# ArduinoUnoShield.net
KiCad netlist of a schematic drawn in Altium Designer
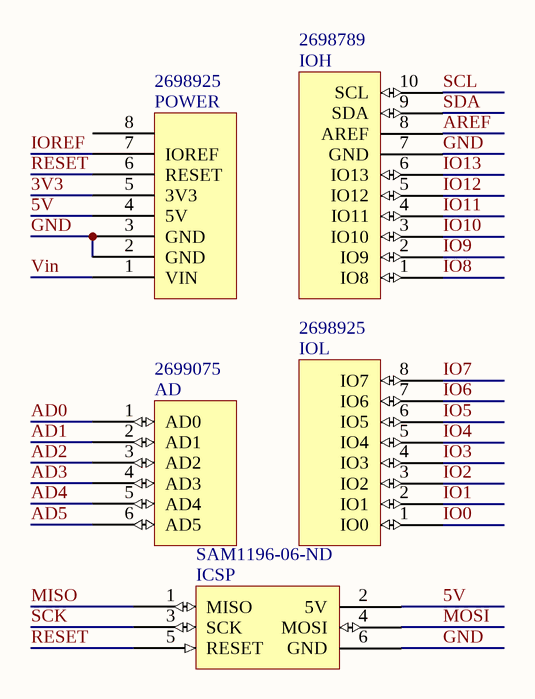
[diagram p0: ArduinoUnoShield.SchDoc]

(export (version "E")
  (design (tool "Eeschema 10.0.6"))
  (components
    (comp (ref "AD")
      (value "AD")
      (footprint "Header:Header 6x1 8.5mm")
      (fields (field (name "SUPPLIER PART NUMBER 4") "2699075"))
      (libsource (lib "Header") (part "AD"))
    )
    (comp (ref "ICSP")
      (value "ICSP")
      (footprint "ICSP")
      (fields (field (name "SUPPLIER PART NUMBER 5") "SAM1196-06-ND"))
      (libsource (lib "Header") (part "ICSP"))
    )
    (comp (ref "IOH")
      (value "IOH")
      (footprint "Header:Header 10x1 8.5mm")
      (fields (field (name "SUPPLIER PART NUMBER 3") "2698789"))
      (libsource (lib "Header") (part "IOH"))
    )
    (comp (ref "IOL")
      (value "IOL")
      (footprint "Header 8x1 8.5mm")
      (fields (field (name "SUPPLIER PART NUMBER 4") "2698925"))
      (libsource (lib "Header") (part "IOL"))
    )
    (comp (ref "POWER")
      (value "POWER_UNO")
      (footprint "Header 8x1 8.5mm")
      (fields (field (name "SUPPLIER PART NUMBER 4") "2698925"))
      (libsource (lib "Header") (part "POWER_UNO"))
    )
  )
  (nets
    (net (code "1") (name "/3V3") (class "Default")
      (node (ref "POWER") (pin "5") (pinfunction "3V3_5") (pintype "power_in"))
    )
    (net (code "2") (name "/5V") (class "Default")
      (node (ref "ICSP") (pin "2") (pinfunction "5V_2") (pintype "power_in"))
      (node (ref "POWER") (pin "4") (pinfunction "5V_4") (pintype "power_in"))
    )
    (net (code "4") (name "/AD0") (class "Default")
      (node (ref "AD") (pin "1") (pinfunction "AD0_1") (pintype "bidirectional"))
    )
    (net (code "5") (name "/AD1") (class "Default")
      (node (ref "AD") (pin "2") (pinfunction "AD1_2") (pintype "bidirectional"))
    )
    (net (code "6") (name "/AD2") (class "Default")
      (node (ref "AD") (pin "3") (pinfunction "AD2_3") (pintype "bidirectional"))
    )
    (net (code "7") (name "/AD3") (class "Default")
      (node (ref "AD") (pin "4") (pinfunction "AD3_4") (pintype "bidirectional"))
    )
    (net (code "8") (name "/AD4") (class "Default")
      (node (ref "AD") (pin "5") (pinfunction "AD4_5") (pintype "bidirectional"))
    )
    (net (code "9") (name "/AD5") (class "Default")
      (node (ref "AD") (pin "6") (pinfunction "AD5_6") (pintype "bidirectional"))
    )
    (net (code "10") (name "/AREF") (class "Default")
      (node (ref "IOH") (pin "8") (pinfunction "AREF_8") (pintype "passive"))
    )
    (net (code "11") (name "/GND") (class "Default")
      (node (ref "ICSP") (pin "6") (pinfunction "GND_6") (pintype "power_in"))
      (node (ref "IOH") (pin "7") (pinfunction "GND_7") (pintype "power_in"))
      (node (ref "POWER") (pin "2") (pinfunction "GND_2") (pintype "power_in"))
      (node (ref "POWER") (pin "3") (pinfunction "GND_3") (pintype "power_in"))
    )
    (net (code "12") (name "/IO0") (class "Default")
      (node (ref "IOL") (pin "1") (pinfunction "IO0_1") (pintype "bidirectional"))
    )
    (net (code "13") (name "/IO1") (class "Default")
      (node (ref "IOL") (pin "2") (pinfunction "IO1_2") (pintype "bidirectional"))
    )
    (net (code "14") (name "/IO2") (class "Default")
      (node (ref "IOL") (pin "3") (pinfunction "IO2_3") (pintype "bidirectional"))
    )
    (net (code "15") (name "/IO3") (class "Default")
      (node (ref "IOL") (pin "4") (pinfunction "IO3_4") (pintype "bidirectional"))
    )
    (net (code "16") (name "/IO4") (class "Default")
      (node (ref "IOL") (pin "5") (pinfunction "IO4_5") (pintype "bidirectional"))
    )
    (net (code "17") (name "/IO5") (class "Default")
      (node (ref "IOL") (pin "6") (pinfunction "IO5_6") (pintype "bidirectional"))
    )
    (net (code "18") (name "/IO6") (class "Default")
      (node (ref "IOL") (pin "7") (pinfunction "IO6_7") (pintype "bidirectional"))
    )
    (net (code "19") (name "/IO7") (class "Default")
      (node (ref "IOL") (pin "8") (pinfunction "IO7_8") (pintype "bidirectional"))
    )
    (net (code "20") (name "/IO8") (class "Default")
      (node (ref "IOH") (pin "1") (pinfunction "IO8_1") (pintype "bidirectional"))
    )
    (net (code "21") (name "/IO9") (class "Default")
      (node (ref "IOH") (pin "2") (pinfunction "IO9_2") (pintype "bidirectional"))
    )
    (net (code "22") (name "/IO10") (class "Default")
      (node (ref "IOH") (pin "3") (pinfunction "IO10_3") (pintype "bidirectional"))
    )
    (net (code "23") (name "/IO11") (class "Default")
      (node (ref "IOH") (pin "4") (pinfunction "IO11_4") (pintype "bidirectional"))
    )
    (net (code "24") (name "/IO12") (class "Default")
      (node (ref "IOH") (pin "5") (pinfunction "IO12_5") (pintype "bidirectional"))
    )
    (net (code "25") (name "/IO13") (class "Default")
      (node (ref "IOH") (pin "6") (pinfunction "IO13_6") (pintype "bidirectional"))
    )
    (net (code "26") (name "/IOREF") (class "Default")
      (node (ref "POWER") (pin "7") (pinfunction "IOREF_7") (pintype "power_in"))
    )
    (net (code "27") (name "/MISO") (class "Default")
      (node (ref "ICSP") (pin "1") (pinfunction "MISO_1") (pintype "bidirectional"))
    )
    (net (code "28") (name "/MOSI") (class "Default")
      (node (ref "ICSP") (pin "4") (pinfunction "MOSI_4") (pintype "bidirectional"))
    )
    (net (code "29") (name "/RESET") (class "Default")
      (node (ref "ICSP") (pin "5") (pinfunction "RESET_5") (pintype "input"))
      (node (ref "POWER") (pin "6") (pinfunction "RESET_6") (pintype "passive"))
    )
    (net (code "30") (name "/SCK") (class "Default")
      (node (ref "ICSP") (pin "3") (pinfunction "SCK_3") (pintype "bidirectional"))
    )
    (net (code "31") (name "/SCL") (class "Default")
      (node (ref "IOH") (pin "10") (pinfunction "SCL_10") (pintype "bidirectional"))
    )
    (net (code "32") (name "/SDA") (class "Default")
      (node (ref "IOH") (pin "9") (pinfunction "SDA_9") (pintype "bidirectional"))
    )
    (net (code "33") (name "/Vin") (class "Default")
      (node (ref "POWER") (pin "1") (pinfunction "VIN_1") (pintype "power_in"))
    )
    (net (code "34") (name "unconnected-(POWER-Pad8)") (class "Default")
      (node (ref "POWER") (pin "8") (pintype "passive"))
    )
  )
)
